# light-meter-B.net
KiCad netlist of a schematic drawn in EAGLE
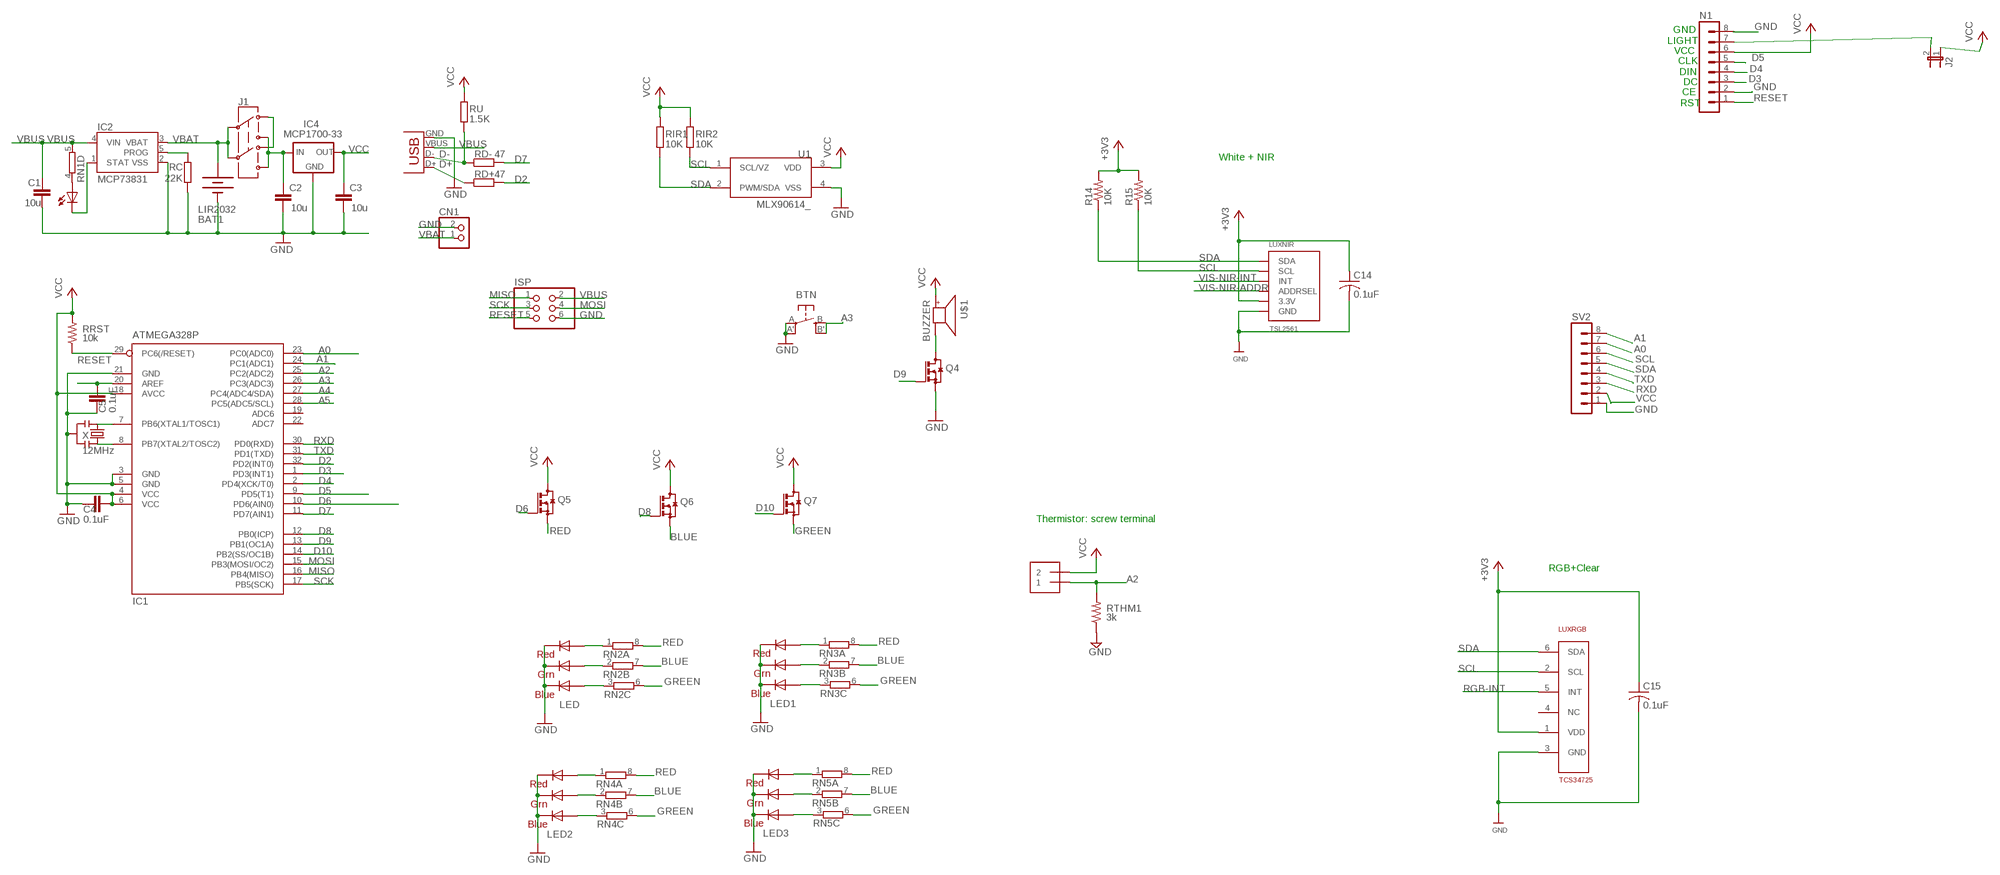
[diagram p0: schematic, sheet 1]

(export (version "E")
  (design (tool "Eeschema 10.0.6"))
  (components
    (comp (ref "BAT1")
      (value "LIR2032")
      (footprint "eagle-import:BATTCOM_20MM_PTH_SMT")
      (libsource (lib "eagle-import") (part "BATTERYBATTCOM_20MM_PTH_SMT"))
    )
    (comp (ref "BTN")
      (value "EVQQ2")
      (footprint "eagle-import:EVQ-Q2")
      (libsource (lib "eagle-import") (part "EVQQ2"))
    )
    (comp (ref "C1")
      (value "10u")
      (footprint "eagle-import:C0805")
      (libsource (lib "eagle-import") (part "resistor_C-EUC0805"))
    )
    (comp (ref "C2")
      (value "10u")
      (footprint "eagle-import:C0805")
      (libsource (lib "eagle-import") (part "resistor_C-EUC0805"))
    )
    (comp (ref "C3")
      (value "10u")
      (footprint "eagle-import:C0805")
      (libsource (lib "eagle-import") (part "resistor_C-EUC0805"))
    )
    (comp (ref "C4")
      (value "0.1uF")
      (footprint "eagle-import:C0805")
      (libsource (lib "eagle-import") (part "C-EUC0805"))
    )
    (comp (ref "C5")
      (value "0.1uF")
      (footprint "eagle-import:C0805")
      (libsource (lib "eagle-import") (part "C-EUC0805"))
    )
    (comp (ref "C14")
      (value "0.1uF")
      (footprint "eagle-import:C0805")
      (libsource (lib "eagle-import") (part "C-USC0805"))
    )
    (comp (ref "C15")
      (value "0.1uF")
      (footprint "eagle-import:C0805")
      (libsource (lib "eagle-import") (part "C-USC0805"))
    )
    (comp (ref "CHG")
      (value "0805")
      (footprint "eagle-import:CHIPLED_0805")
      (libsource (lib "eagle-import") (part "LEDCHIPLED_0805"))
    )
    (comp (ref "CN1")
      (value "JST_2PIN-SMT-RA")
      (footprint "eagle-import:JST-PH-2-SMT-RA")
      (libsource (lib "eagle-import") (part "JST_2PIN-SMT-RA"))
    )
    (comp (ref "IC1")
      (value "ATMEGA328P")
      (footprint "eagle-import:TQFP32-08")
      (fields (field (name "MPN") "ATMEGA8-16AU"))
      (libsource (lib "eagle-import") (part "MEGA8-AI"))
    )
    (comp (ref "IC2")
      (value "MCP73831")
      (footprint "eagle-import:SOT23-5")
      (libsource (lib "eagle-import") (part "MCP73831"))
    )
    (comp (ref "IC4")
      (value "MCP1700-33")
      (footprint "eagle-import:SOT23")
      (libsource (lib "eagle-import") (part "MCP1700SOT233"))
    )
    (comp (ref "ISP")
      (value "PINHD-2X3")
      (footprint "eagle-import:2X03")
      (libsource (lib "eagle-import") (part "PINHD-2X3"))
    )
    (comp (ref "J1")
      (value "AYZ0202")
      (footprint "eagle-import:AYZ0202")
      (libsource (lib "eagle-import") (part "AYZ0202"))
    )
    (comp (ref "J2")
      (value "JP1E")
      (footprint "eagle-import:JP1")
      (libsource (lib "eagle-import") (part "JP1E"))
    )
    (comp (ref "LED")
      (value "RGBLED5050")
      (footprint "eagle-import:RGBLED5050")
      (libsource (lib "eagle-import") (part "RGBLED5050"))
    )
    (comp (ref "LED1")
      (value "RGBLED5050")
      (footprint "eagle-import:RGBLED5050")
      (libsource (lib "eagle-import") (part "RGBLED5050"))
    )
    (comp (ref "LED2")
      (value "RGBLED5050")
      (footprint "eagle-import:RGBLED5050")
      (libsource (lib "eagle-import") (part "RGBLED5050"))
    )
    (comp (ref "LED3")
      (value "RGBLED5050")
      (footprint "eagle-import:RGBLED5050")
      (libsource (lib "eagle-import") (part "RGBLED5050"))
    )
    (comp (ref "LUXNIR")
      (value "TSL2561")
      (footprint "eagle-import:TSL2561_FN@1")
      (libsource (lib "eagle-import") (part "TSL2561"))
    )
    (comp (ref "LUXRGB")
      (value "TCS34725")
      (footprint "eagle-import:DFN-6")
      (libsource (lib "eagle-import") (part "TCS34725"))
    )
    (comp (ref "N1")
      (value "MA08-1")
      (footprint "eagle-import:MA08-1")
      (libsource (lib "eagle-import") (part "MA08-1"))
    )
    (comp (ref "Q4")
      (value "BSS123")
      (footprint "eagle-import:SOT23")
      (libsource (lib "eagle-import") (part "BSS123"))
    )
    (comp (ref "Q5")
      (value "BSS123")
      (footprint "eagle-import:SOT23")
      (libsource (lib "eagle-import") (part "BSS123"))
    )
    (comp (ref "Q6")
      (value "BSS123")
      (footprint "eagle-import:SOT23")
      (libsource (lib "eagle-import") (part "BSS123"))
    )
    (comp (ref "Q7")
      (value "BSS123")
      (footprint "eagle-import:SOT23")
      (libsource (lib "eagle-import") (part "BSS123"))
    )
    (comp (ref "R14")
      (value "10K")
      (footprint "eagle-import:R0805")
      (libsource (lib "eagle-import") (part "R-US_R0805"))
    )
    (comp (ref "R15")
      (value "10K")
      (footprint "eagle-import:R0805")
      (libsource (lib "eagle-import") (part "R-US_R0805"))
    )
    (comp (ref "RC")
      (value "22K")
      (footprint "eagle-import:R0805")
      (libsource (lib "eagle-import") (part "R-EU_R0805"))
    )
    (comp (ref "RD+")
      (value "47")
      (footprint "eagle-import:R0805")
      (libsource (lib "eagle-import") (part "R-EU_R0805"))
    )
    (comp (ref "RD-")
      (value "47")
      (footprint "eagle-import:R0805")
      (libsource (lib "eagle-import") (part "R-EU_R0805"))
    )
    (comp (ref "RIR1")
      (value "10K")
      (footprint "eagle-import:R0805")
      (libsource (lib "eagle-import") (part "R-EU_R0805"))
    )
    (comp (ref "RIR2")
      (value "10K")
      (footprint "eagle-import:R0805")
      (libsource (lib "eagle-import") (part "R-EU_R0805"))
    )
    (comp (ref "RN1")
      (value "4R-NEXB38V")
      (footprint "eagle-import:EXB38V")
      (libsource (lib "eagle-import") (part "4R-NEXB38V"))
    )
    (comp (ref "RN2")
      (value "4R-NEXB38V")
      (footprint "eagle-import:EXB38V")
      (libsource (lib "eagle-import") (part "4R-NEXB38V"))
    )
    (comp (ref "RN3")
      (value "4R-NEXB38V")
      (footprint "eagle-import:EXB38V")
      (libsource (lib "eagle-import") (part "4R-NEXB38V"))
    )
    (comp (ref "RN4")
      (value "4R-NEXB38V")
      (footprint "eagle-import:EXB38V")
      (libsource (lib "eagle-import") (part "4R-NEXB38V"))
    )
    (comp (ref "RN5")
      (value "4R-NEXB38V")
      (footprint "eagle-import:EXB38V")
      (libsource (lib "eagle-import") (part "4R-NEXB38V"))
    )
    (comp (ref "RRST")
      (value "10k")
      (footprint "eagle-import:R0805@1")
      (libsource (lib "eagle-import") (part "rcl_R-US_R0805"))
    )
    (comp (ref "RTHM1")
      (value "3k")
      (footprint "eagle-import:R0805@1")
      (libsource (lib "eagle-import") (part "rcl_R-US_R0805"))
    )
    (comp (ref "RU")
      (value "1.5K")
      (footprint "eagle-import:R0805")
      (libsource (lib "eagle-import") (part "R-EU_R0805"))
    )
    (comp (ref "SV2")
      (value "MA08-1")
      (footprint "eagle-import:MA08-1")
      (libsource (lib "eagle-import") (part "MA08-1"))
    )
    (comp (ref "THM1")
      (value "1X2-3.5MM")
      (footprint "eagle-import:1X2-3.5MM")
      (libsource (lib "eagle-import") (part "1X2-3.5MM"))
    )
    (comp (ref "U$1")
      (value "BUZZER")
      (footprint "eagle-import:SMT-8585-BUZZER")
      (libsource (lib "eagle-import") (part "BUZZER"))
    )
    (comp (ref "U1")
      (value "MLX90614_")
      (footprint "eagle-import:TO-39")
      (libsource (lib "eagle-import") (part "MLX90614_"))
    )
    (comp (ref "X")
      (value "12MHz")
      (footprint "eagle-import:RESONATOR-SMD")
      (libsource (lib "eagle-import") (part "RESONATORSMD"))
    )
    (comp (ref "X1")
      (value "USBSMD")
      (footprint "eagle-import:USB-MINIB")
      (libsource (lib "eagle-import") (part "USBSMD"))
    )
  )
  (nets
    (net (code "1") (name "+3V3") (class "Default")
      (node (ref "C14") (pin "1") (pinfunction "1_1") (pintype "passive"))
      (node (ref "C15") (pin "1") (pinfunction "1_1") (pintype "passive"))
      (node (ref "LUXNIR") (pin "VDD") (pinfunction "3.3V_VDD") (pintype "bidirectional"))
      (node (ref "LUXRGB") (pin "1") (pinfunction "VDD_1") (pintype "bidirectional"))
      (node (ref "R14") (pin "2") (pinfunction "2_2") (pintype "passive"))
      (node (ref "R15") (pin "2") (pinfunction "2_2") (pintype "passive"))
    )
    (net (code "2") (name "/A0") (class "Default")
      (node (ref "IC1") (pin "23") (pinfunction "PC0(ADC0)_23") (pintype "bidirectional"))
      (node (ref "SV2") (pin "7") (pinfunction "7_7") (pintype "passive"))
    )
    (net (code "3") (name "/A1") (class "Default")
      (node (ref "IC1") (pin "24") (pinfunction "PC1(ADC1)_24") (pintype "bidirectional"))
      (node (ref "SV2") (pin "8") (pinfunction "8_8") (pintype "passive"))
    )
    (net (code "4") (name "/A2") (class "Default")
      (node (ref "IC1") (pin "25") (pinfunction "PC2(ADC2)_25") (pintype "bidirectional"))
      (node (ref "RTHM1") (pin "2") (pinfunction "2_2") (pintype "passive"))
      (node (ref "THM1") (pin "1") (pinfunction "1_1") (pintype "passive"))
    )
    (net (code "5") (name "/A3") (class "Default")
      (node (ref "BTN") (pin "B") (pinfunction "S_B") (pintype "passive"))
      (node (ref "BTN") (pin "B'") (pinfunction "S1_B'") (pintype "passive"))
      (node (ref "IC1") (pin "26") (pinfunction "PC3(ADC3)_26") (pintype "bidirectional"))
    )
    (net (code "6") (name "/A4") (class "Default")
      (node (ref "IC1") (pin "27") (pinfunction "PC4(ADC4/SDA)_27") (pintype "bidirectional"))
    )
    (net (code "7") (name "/A5") (class "Default")
      (node (ref "IC1") (pin "28") (pinfunction "PC5(ADC5/SCL)_28") (pintype "bidirectional"))
    )
    (net (code "8") (name "/BLUE") (class "Default")
      (node (ref "Q6") (pin "2") (pinfunction "S_2") (pintype "passive"))
      (node (ref "RN2") (pin "7") (pinfunction "2_7") (pintype "passive"))
      (node (ref "RN3") (pin "7") (pinfunction "2_7") (pintype "passive"))
      (node (ref "RN4") (pin "7") (pinfunction "2_7") (pintype "passive"))
      (node (ref "RN5") (pin "7") (pinfunction "2_7") (pintype "passive"))
    )
    (net (code "9") (name "/D+") (class "Default")
      (node (ref "RD+") (pin "1") (pinfunction "1_1") (pintype "passive"))
      (node (ref "X1") (pin "D+") (pinfunction "D+_D+") (pintype "bidirectional"))
    )
    (net (code "10") (name "/D-") (class "Default")
      (node (ref "RD-") (pin "1") (pinfunction "1_1") (pintype "passive"))
      (node (ref "RU") (pin "1") (pinfunction "1_1") (pintype "passive"))
      (node (ref "X1") (pin "D-") (pinfunction "D-_D-") (pintype "bidirectional"))
    )
    (net (code "11") (name "/D2") (class "Default")
      (node (ref "IC1") (pin "32") (pinfunction "PD2(INT0)_32") (pintype "bidirectional"))
      (node (ref "RD+") (pin "2") (pinfunction "2_2") (pintype "passive"))
    )
    (net (code "12") (name "/D3") (class "Default")
      (node (ref "IC1") (pin "1") (pinfunction "PD3(INT1)_1") (pintype "bidirectional"))
      (node (ref "N1") (pin "3") (pinfunction "3_3") (pintype "passive"))
    )
    (net (code "13") (name "/D4") (class "Default")
      (node (ref "IC1") (pin "2") (pinfunction "PD4(XCK/T0)_2") (pintype "bidirectional"))
      (node (ref "N1") (pin "4") (pinfunction "4_4") (pintype "passive"))
    )
    (net (code "14") (name "/D5") (class "Default")
      (node (ref "IC1") (pin "9") (pinfunction "PD5(T1)_9") (pintype "bidirectional"))
      (node (ref "N1") (pin "5") (pinfunction "5_5") (pintype "passive"))
    )
    (net (code "15") (name "/D6") (class "Default")
      (node (ref "IC1") (pin "10") (pinfunction "PD6(AIN0)_10") (pintype "bidirectional"))
      (node (ref "Q5") (pin "1") (pinfunction "G_1") (pintype "passive"))
    )
    (net (code "16") (name "/D7") (class "Default")
      (node (ref "IC1") (pin "11") (pinfunction "PD7(AIN1)_11") (pintype "bidirectional"))
      (node (ref "RD-") (pin "2") (pinfunction "2_2") (pintype "passive"))
    )
    (net (code "17") (name "/D8") (class "Default")
      (node (ref "IC1") (pin "12") (pinfunction "PB0(ICP)_12") (pintype "bidirectional"))
      (node (ref "Q6") (pin "1") (pinfunction "G_1") (pintype "passive"))
    )
    (net (code "18") (name "/D9") (class "Default")
      (node (ref "IC1") (pin "13") (pinfunction "PB1(OC1A)_13") (pintype "bidirectional"))
      (node (ref "Q4") (pin "1") (pinfunction "G_1") (pintype "passive"))
    )
    (net (code "19") (name "/D10") (class "Default")
      (node (ref "IC1") (pin "14") (pinfunction "PB2(SS/OC1B)_14") (pintype "bidirectional"))
      (node (ref "Q7") (pin "1") (pinfunction "G_1") (pintype "passive"))
    )
    (net (code "20") (name "/GREEN") (class "Default")
      (node (ref "Q7") (pin "2") (pinfunction "S_2") (pintype "passive"))
      (node (ref "RN2") (pin "6") (pinfunction "2_6") (pintype "passive"))
      (node (ref "RN3") (pin "6") (pinfunction "2_6") (pintype "passive"))
      (node (ref "RN4") (pin "6") (pinfunction "2_6") (pintype "passive"))
      (node (ref "RN5") (pin "6") (pinfunction "2_6") (pintype "passive"))
    )
    (net (code "21") (name "/MISO") (class "Default")
      (node (ref "IC1") (pin "16") (pinfunction "PB4(MISO)_16") (pintype "bidirectional"))
      (node (ref "ISP") (pin "1") (pinfunction "1_1") (pintype "passive"))
    )
    (net (code "22") (name "/MOSI") (class "Default")
      (node (ref "IC1") (pin "15") (pinfunction "PB3(MOSI/OC2)_15") (pintype "bidirectional"))
      (node (ref "ISP") (pin "4") (pinfunction "4_4") (pintype "passive"))
    )
    (net (code "23") (name "/RED") (class "Default")
      (node (ref "Q5") (pin "2") (pinfunction "S_2") (pintype "passive"))
      (node (ref "RN2") (pin "8") (pinfunction "2_8") (pintype "passive"))
      (node (ref "RN3") (pin "8") (pinfunction "2_8") (pintype "passive"))
      (node (ref "RN4") (pin "8") (pinfunction "2_8") (pintype "passive"))
      (node (ref "RN5") (pin "8") (pinfunction "2_8") (pintype "passive"))
    )
    (net (code "24") (name "/RESET") (class "Default")
      (node (ref "IC1") (pin "29") (pinfunction "PC6(/RESET)_29") (pintype "bidirectional"))
      (node (ref "ISP") (pin "5") (pinfunction "5_5") (pintype "passive"))
      (node (ref "N1") (pin "1") (pinfunction "1_1") (pintype "passive"))
      (node (ref "RRST") (pin "1") (pinfunction "1_1") (pintype "passive"))
    )
    (net (code "25") (name "/RGB-INT") (class "Default")
      (node (ref "LUXRGB") (pin "5") (pinfunction "INT_5") (pintype "bidirectional"))
    )
    (net (code "26") (name "/RXD") (class "Default")
      (node (ref "IC1") (pin "30") (pinfunction "PD0(RXD)_30") (pintype "bidirectional"))
      (node (ref "SV2") (pin "3") (pinfunction "3_3") (pintype "passive"))
    )
    (net (code "27") (name "/SCK") (class "Default")
      (node (ref "IC1") (pin "17") (pinfunction "PB5(SCK)_17") (pintype "bidirectional"))
      (node (ref "ISP") (pin "3") (pinfunction "3_3") (pintype "passive"))
    )
    (net (code "28") (name "/SCL") (class "Default")
      (node (ref "LUXNIR") (pin "CLK") (pinfunction "SCL_CLK") (pintype "bidirectional"))
      (node (ref "LUXRGB") (pin "2") (pinfunction "SCL_2") (pintype "bidirectional"))
      (node (ref "R15") (pin "1") (pinfunction "1_1") (pintype "passive"))
      (node (ref "RIR2") (pin "1") (pinfunction "1_1") (pintype "passive"))
      (node (ref "SV2") (pin "6") (pinfunction "6_6") (pintype "passive"))
      (node (ref "U1") (pin "1") (pinfunction "SCL/VZ_1") (pintype "bidirectional"))
    )
    (net (code "29") (name "/SDA") (class "Default")
      (node (ref "LUXNIR") (pin "DATA") (pinfunction "SDA_DATA") (pintype "bidirectional"))
      (node (ref "LUXRGB") (pin "6") (pinfunction "SDA_6") (pintype "bidirectional"))
      (node (ref "R14") (pin "1") (pinfunction "1_1") (pintype "passive"))
      (node (ref "RIR1") (pin "1") (pinfunction "1_1") (pintype "passive"))
      (node (ref "SV2") (pin "5") (pinfunction "5_5") (pintype "passive"))
      (node (ref "U1") (pin "2") (pinfunction "PWM/SDA_2") (pintype "bidirectional"))
    )
    (net (code "30") (name "/TXD") (class "Default")
      (node (ref "IC1") (pin "31") (pinfunction "PD1(TXD)_31") (pintype "bidirectional"))
      (node (ref "SV2") (pin "4") (pinfunction "4_4") (pintype "passive"))
    )
    (net (code "31") (name "/VBAT") (class "Default")
      (node (ref "BAT1") (pin "P$2") (pinfunction "+_P$2") (pintype "power_in"))
      (node (ref "CN1") (pin "1") (pinfunction "2_1") (pintype "passive"))
      (node (ref "IC2") (pin "3") (pinfunction "VBAT_3") (pintype "power_in"))
      (node (ref "J1") (pin "2") (pinfunction "2_2") (pintype "bidirectional"))
      (node (ref "J1") (pin "5") (pinfunction "5_5") (pintype "bidirectional"))
    )
    (net (code "32") (name "/VBUS") (class "Default")
      (node (ref "C1") (pin "1") (pinfunction "1_1") (pintype "passive"))
      (node (ref "IC2") (pin "4") (pinfunction "VIN_4") (pintype "power_in"))
      (node (ref "ISP") (pin "2") (pinfunction "2_2") (pintype "passive"))
      (node (ref "RN1") (pin "5") (pinfunction "2_5") (pintype "passive"))
      (node (ref "X1") (pin "VBUS") (pinfunction "VBUS_VBUS") (pintype "bidirectional"))
    )
    (net (code "33") (name "/VIS-NIR-ADDR") (class "Default")
      (node (ref "LUXNIR") (pin "ADR") (pinfunction "ADDRSEL_ADR") (pintype "bidirectional"))
    )
    (net (code "34") (name "/VIS-NIR-INT") (class "Default")
      (node (ref "LUXNIR") (pin "INT") (pinfunction "INT_INT") (pintype "bidirectional"))
    )
    (net (code "35") (name "GND") (class "Default")
      (node (ref "BAT1") (pin "P$1") (pinfunction "-_P$1") (pintype "power_in"))
      (node (ref "BTN") (pin "A") (pinfunction "P_A") (pintype "passive"))
      (node (ref "BTN") (pin "A'") (pinfunction "P1_A'") (pintype "passive"))
      (node (ref "C1") (pin "2") (pinfunction "2_2") (pintype "passive"))
      (node (ref "C14") (pin "2") (pinfunction "2_2") (pintype "passive"))
      (node (ref "C15") (pin "2") (pinfunction "2_2") (pintype "passive"))
      (node (ref "C2") (pin "2") (pinfunction "2_2") (pintype "passive"))
      (node (ref "C3") (pin "2") (pinfunction "2_2") (pintype "passive"))
      (node (ref "C4") (pin "1") (pinfunction "1_1") (pintype "passive"))
      (node (ref "C5") (pin "1") (pinfunction "1_1") (pintype "passive"))
      (node (ref "CN1") (pin "2") (pinfunction "1_2") (pintype "passive"))
      (node (ref "IC1") (pin "21") (pinfunction "GND_21") (pintype "power_in"))
      (node (ref "IC1") (pin "3") (pinfunction "GND_3") (pintype "power_in"))
      (node (ref "IC1") (pin "5") (pinfunction "GND_5") (pintype "power_in"))
      (node (ref "IC2") (pin "2") (pinfunction "VSS_2") (pintype "power_in"))
      (node (ref "IC4") (pin "1") (pinfunction "GND_1") (pintype "input"))
      (node (ref "ISP") (pin "6") (pinfunction "6_6") (pintype "passive"))
      (node (ref "LED") (pin "4") (pinfunction "BLUE_C_4") (pintype "bidirectional"))
      (node (ref "LED") (pin "5") (pinfunction "RED_C_5") (pintype "bidirectional"))
      (node (ref "LED") (pin "6") (pinfunction "GREEN_C_6") (pintype "bidirectional"))
      (node (ref "LED1") (pin "4") (pinfunction "BLUE_C_4") (pintype "bidirectional"))
      (node (ref "LED1") (pin "5") (pinfunction "RED_C_5") (pintype "bidirectional"))
      (node (ref "LED1") (pin "6") (pinfunction "GREEN_C_6") (pintype "bidirectional"))
      (node (ref "LED2") (pin "4") (pinfunction "BLUE_C_4") (pintype "bidirectional"))
      (node (ref "LED2") (pin "5") (pinfunction "RED_C_5") (pintype "bidirectional"))
      (node (ref "LED2") (pin "6") (pinfunction "GREEN_C_6") (pintype "bidirectional"))
      (node (ref "LED3") (pin "4") (pinfunction "BLUE_C_4") (pintype "bidirectional"))
      (node (ref "LED3") (pin "5") (pinfunction "RED_C_5") (pintype "bidirectional"))
      (node (ref "LED3") (pin "6") (pinfunction "GREEN_C_6") (pintype "bidirectional"))
      (node (ref "LUXNIR") (pin "VSS") (pinfunction "GND_VSS") (pintype "bidirectional"))
      (node (ref "LUXRGB") (pin "3") (pinfunction "GND_3") (pintype "bidirectional"))
      (node (ref "N1") (pin "2") (pinfunction "2_2") (pintype "passive"))
      (node (ref "N1") (pin "8") (pinfunction "8_8") (pintype "passive"))
      (node (ref "Q4") (pin "2") (pinfunction "S_2") (pintype "passive"))
      (node (ref "RC") (pin "1") (pinfunction "1_1") (pintype "passive"))
      (node (ref "RTHM1") (pin "1") (pinfunction "1_1") (pintype "passive"))
      (node (ref "SV2") (pin "1") (pinfunction "1_1") (pintype "passive"))
      (node (ref "U1") (pin "4") (pinfunction "VSS_4") (pintype "bidirectional"))
      (node (ref "X") (pin "2") (pinfunction "2_2") (pintype "passive"))
      (node (ref "X1") (pin "GND") (pinfunction "GND_GND") (pintype "bidirectional"))
    )
    (net (code "36") (name "Net-(IC1-AREF)") (class "Default")
      (node (ref "C5") (pin "2") (pinfunction "2_2") (pintype "passive"))
      (node (ref "IC1") (pin "20") (pinfunction "AREF_20") (pintype "passive"))
    )
    (net (code "37") (name "Net-(IC1-PB6(XTAL1{slash}TOSC1))") (class "Default")
      (node (ref "IC1") (pin "7") (pinfunction "PB6(XTAL1/TOSC1)_7") (pintype "bidirectional"))
      (node (ref "X") (pin "1") (pinfunction "1_1") (pintype "passive"))
    )
    (net (code "38") (name "Net-(IC1-PB7(XTAL2{slash}TOSC2))") (class "Default")
      (node (ref "IC1") (pin "8") (pinfunction "PB7(XTAL2/TOSC2)_8") (pintype "bidirectional"))
      (node (ref "X") (pin "3") (pinfunction "3_3") (pintype "passive"))
    )
    (net (code "39") (name "Net-(IC2-PROG)") (class "Default")
      (node (ref "IC2") (pin "5") (pinfunction "PROG_5") (pintype "input"))
      (node (ref "RC") (pin "2") (pinfunction "2_2") (pintype "passive"))
    )
    (net (code "40") (name "Net-(IC2-STAT)") (class "Default")
      (node (ref "CHG") (pin "C") (pinfunction "C_C") (pintype "passive"))
      (node (ref "IC2") (pin "1") (pinfunction "STAT_1") (pintype "output"))
    )
    (net (code "41") (name "Net-(IC4-IN)") (class "Default")
      (node (ref "C2") (pin "1") (pinfunction "1_1") (pintype "passive"))
      (node (ref "IC4") (pin "3") (pinfunction "IN_3") (pintype "input"))
      (node (ref "J1") (pin "1") (pinfunction "3_1") (pintype "bidirectional"))
      (node (ref "J1") (pin "4") (pinfunction "6_4") (pintype "bidirectional"))
    )
    (net (code "42") (name "Net-(J1-1)") (class "Default")
      (node (ref "J1") (pin "3") (pinfunction "1_3") (pintype "bidirectional"))
      (node (ref "J1") (pin "6") (pinfunction "4_6") (pintype "bidirectional"))
    )
    (net (code "43") (name "Net-(J2-Pad2)") (class "Default")
      (node (ref "J2") (pin "2") (pinfunction "2_2") (pintype "passive"))
      (node (ref "N1") (pin "7") (pinfunction "7_7") (pintype "passive"))
    )
    (net (code "44") (name "Net-(LED-BLUE_A)") (class "Default")
      (node (ref "LED") (pin "3") (pinfunction "BLUE_A_3") (pintype "bidirectional"))
      (node (ref "RN2") (pin "3") (pinfunction "1_3") (pintype "passive"))
    )
    (net (code "45") (name "Net-(LED-GREEN_A)") (class "Default")
      (node (ref "LED") (pin "1") (pinfunction "GREEN_A_1") (pintype "bidirectional"))
      (node (ref "RN2") (pin "2") (pinfunction "1_2") (pintype "passive"))
    )
    (net (code "46") (name "Net-(LED-RED_A)") (class "Default")
      (node (ref "LED") (pin "2") (pinfunction "RED_A_2") (pintype "bidirectional"))
      (node (ref "RN2") (pin "1") (pinfunction "1_1") (pintype "passive"))
    )
    (net (code "47") (name "Net-(LED1-BLUE_A)") (class "Default")
      (node (ref "LED1") (pin "3") (pinfunction "BLUE_A_3") (pintype "bidirectional"))
      (node (ref "RN3") (pin "3") (pinfunction "1_3") (pintype "passive"))
    )
    (net (code "48") (name "Net-(LED1-GREEN_A)") (class "Default")
      (node (ref "LED1") (pin "1") (pinfunction "GREEN_A_1") (pintype "bidirectional"))
      (node (ref "RN3") (pin "2") (pinfunction "1_2") (pintype "passive"))
    )
    (net (code "49") (name "Net-(LED1-RED_A)") (class "Default")
      (node (ref "LED1") (pin "2") (pinfunction "RED_A_2") (pintype "bidirectional"))
      (node (ref "RN3") (pin "1") (pinfunction "1_1") (pintype "passive"))
    )
    (net (code "50") (name "Net-(LED2-BLUE_A)") (class "Default")
      (node (ref "LED2") (pin "3") (pinfunction "BLUE_A_3") (pintype "bidirectional"))
      (node (ref "RN4") (pin "3") (pinfunction "1_3") (pintype "passive"))
    )
    (net (code "51") (name "Net-(LED2-GREEN_A)") (class "Default")
      (node (ref "LED2") (pin "1") (pinfunction "GREEN_A_1") (pintype "bidirectional"))
      (node (ref "RN4") (pin "2") (pinfunction "1_2") (pintype "passive"))
    )
    (net (code "52") (name "Net-(LED2-RED_A)") (class "Default")
      (node (ref "LED2") (pin "2") (pinfunction "RED_A_2") (pintype "bidirectional"))
      (node (ref "RN4") (pin "1") (pinfunction "1_1") (pintype "passive"))
    )
    (net (code "53") (name "Net-(LED3-BLUE_A)") (class "Default")
      (node (ref "LED3") (pin "3") (pinfunction "BLUE_A_3") (pintype "bidirectional"))
      (node (ref "RN5") (pin "3") (pinfunction "1_3") (pintype "passive"))
    )
    (net (code "54") (name "Net-(LED3-GREEN_A)") (class "Default")
      (node (ref "LED3") (pin "1") (pinfunction "GREEN_A_1") (pintype "bidirectional"))
      (node (ref "RN5") (pin "2") (pinfunction "1_2") (pintype "passive"))
    )
    (net (code "55") (name "Net-(LED3-RED_A)") (class "Default")
      (node (ref "LED3") (pin "2") (pinfunction "RED_A_2") (pintype "bidirectional"))
      (node (ref "RN5") (pin "1") (pinfunction "1_1") (pintype "passive"))
    )
    (net (code "56") (name "Net-(Q4-D)") (class "Default")
      (node (ref "Q4") (pin "3") (pinfunction "D_3") (pintype "passive"))
      (node (ref "U$1") (pin "-") (pinfunction "-_-") (pintype "passive"))
    )
    (net (code "57") (name "Net-(RN1D-1)") (class "Default")
      (node (ref "CHG") (pin "A") (pinfunction "A_A") (pintype "passive"))
      (node (ref "RN1") (pin "4") (pinfunction "1_4") (pintype "passive"))
    )
    (net (code "58") (name "VCC") (class "Default")
      (node (ref "C3") (pin "1") (pinfunction "1_1") (pintype "passive"))
      (node (ref "C4") (pin "2") (pinfunction "2_2") (pintype "passive"))
      (node (ref "IC1") (pin "18") (pinfunction "AVCC_18") (pintype "power_in"))
      (node (ref "IC1") (pin "4") (pinfunction "VCC_4") (pintype "power_in"))
      (node (ref "IC1") (pin "6") (pinfunction "VCC_6") (pintype "power_in"))
      (node (ref "IC4") (pin "2") (pinfunction "OUT_2") (pintype "passive"))
      (node (ref "J2") (pin "1") (pinfunction "1_1") (pintype "passive"))
      (node (ref "N1") (pin "6") (pinfunction "6_6") (pintype "passive"))
      (node (ref "Q5") (pin "3") (pinfunction "D_3") (pintype "passive"))
      (node (ref "Q6") (pin "3") (pinfunction "D_3") (pintype "passive"))
      (node (ref "Q7") (pin "3") (pinfunction "D_3") (pintype "passive"))
      (node (ref "RIR1") (pin "2") (pinfunction "2_2") (pintype "passive"))
      (node (ref "RIR2") (pin "2") (pinfunction "2_2") (pintype "passive"))
      (node (ref "RRST") (pin "2") (pinfunction "2_2") (pintype "passive"))
      (node (ref "RU") (pin "2") (pinfunction "2_2") (pintype "passive"))
      (node (ref "SV2") (pin "2") (pinfunction "2_2") (pintype "passive"))
      (node (ref "THM1") (pin "2") (pinfunction "2_2") (pintype "passive"))
      (node (ref "U$1") (pin "+") (pinfunction "+_+") (pintype "passive"))
      (node (ref "U1") (pin "3") (pinfunction "VDD_3") (pintype "bidirectional"))
    )
    (net (code "59") (name "unconnected-(IC1-ADC6-Pad19)") (class "Default")
      (node (ref "IC1") (pin "19") (pinfunction "ADC6_19") (pintype "bidirectional"))
    )
    (net (code "60") (name "unconnected-(IC1-ADC7-Pad22)") (class "Default")
      (node (ref "IC1") (pin "22") (pinfunction "ADC7_22") (pintype "bidirectional"))
    )
    (net (code "61") (name "unconnected-(LUXRGB-NC-Pad4)") (class "Default")
      (node (ref "LUXRGB") (pin "4") (pinfunction "NC_4") (pintype "bidirectional"))
    )
  )
)
